# machkhoasodientu.net
KiCad netlist of a schematic drawn in Altium Designer
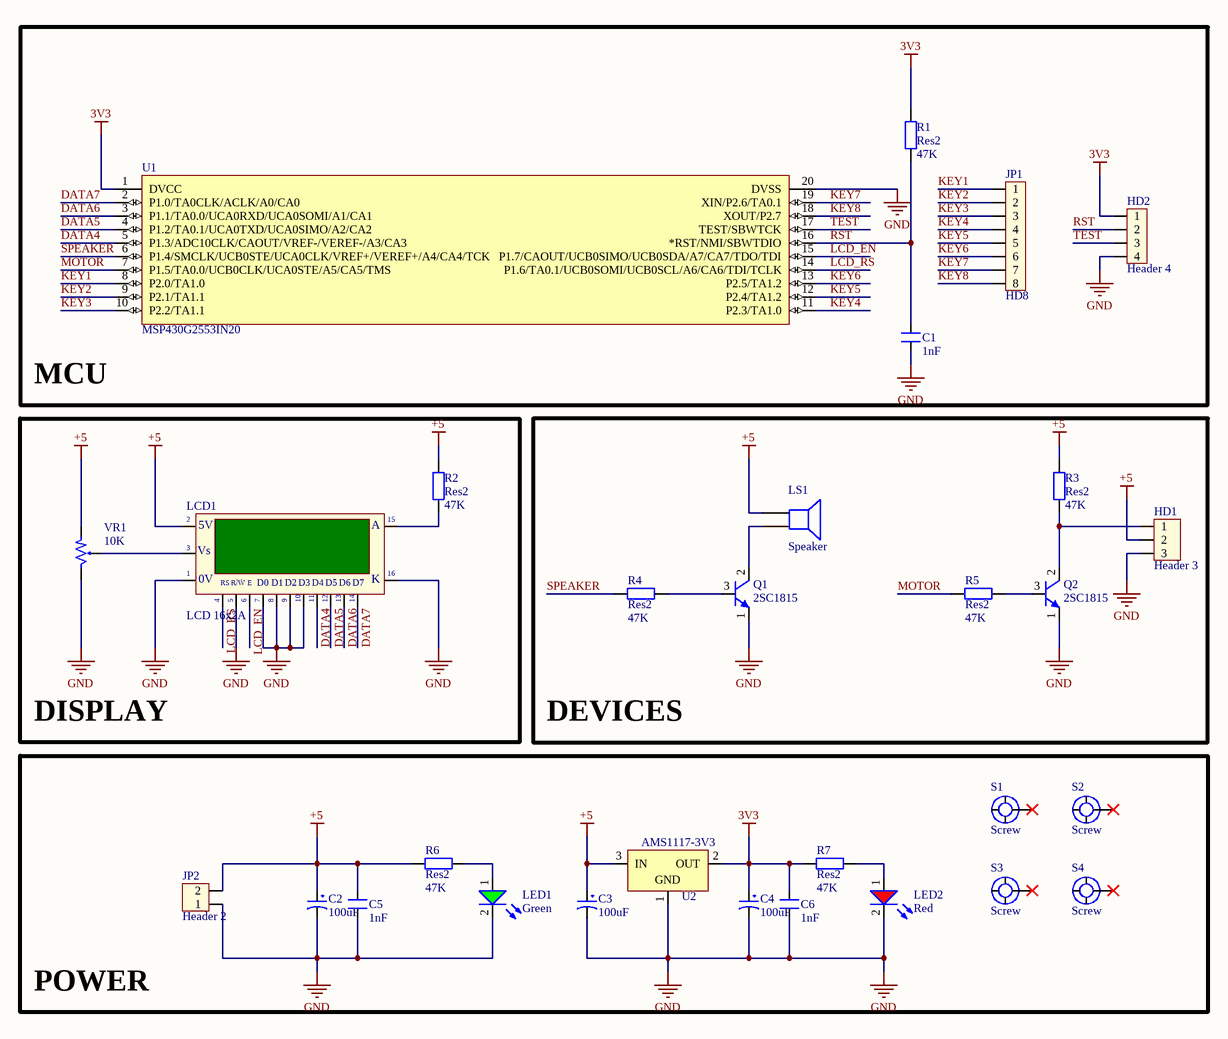
[diagram p0: machkhoasodientu.SchDoc]

(export (version "E")
  (design (tool "Eeschema 10.0.6"))
  (components
    (comp (ref "C1")
      (value "1nF")
      (footprint "CN1")
      (description "Cap np  1pF - 472pF")
      (libsource (lib "lpson") (part "CN1"))
    )
    (comp (ref "C2")
      (value "100uF")
      (footprint "CP1/2.5")
      (description "C 47uF/50V , 220uF/16V")
      (libsource (lib "lpson") (part "CP2"))
    )
    (comp (ref "C3")
      (value "100uF")
      (footprint "CP1/2.5")
      (description "C 47uF/50V , 220uF/16V")
      (libsource (lib "lpson") (part "CP2"))
    )
    (comp (ref "C4")
      (value "100uF")
      (footprint "CP1/2.5")
      (description "C 47uF/50V , 220uF/16V")
      (libsource (lib "lpson") (part "CP2"))
    )
    (comp (ref "C5")
      (value "1nF")
      (footprint "CN1")
      (description "Cap np  1pF - 472pF")
      (libsource (lib "lpson") (part "CN1"))
    )
    (comp (ref "C6")
      (value "1nF")
      (footprint "CN1")
      (description "Cap np  1pF - 472pF")
      (libsource (lib "lpson") (part "CN1"))
    )
    (comp (ref "HD1") (value "Header 3") (footprint "Header_3") (libsource (lib "lpson") (part "Header3")))
    (comp (ref "HD2") (value "Header 4") (footprint "Header_4") (libsource (lib "lpson") (part "Header4")))
    (comp (ref "JP1")
      (value "HD8")
      (footprint "Header_8")
      (description "Header 8")
      (fields (field (name "CREAT BY") "VanDungEvn@Gmail.com"))
      (libsource (lib "lpson") (part "Header8"))
    )
    (comp (ref "JP2") (value "Header 2") (footprint "Header_2") (libsource (lib "lpson") (part "Header2")))
    (comp (ref "LCD1")
      (value "LCD 16x2A")
      (footprint "LCD16x2")
      (description "LCD dipslay 16 char, 2 line")
      (libsource (lib "lpson") (part "LCD16x2A"))
    )
    (comp (ref "LED1")
      (value "Green")
      (footprint "LED3G")
      (description "LED Green 3mm")
      (fields (field (name "Comment") "LED_G_3"))
      (libsource (lib "lpson") (part "LED_GREEN_3MM"))
    )
    (comp (ref "LED2")
      (value "Red")
      (footprint "LED3R")
      (description "LED Red 3mm")
      (fields (field (name "Comment") "LED_R_3"))
      (libsource (lib "lpson") (part "LED_RED_3MM"))
    )
    (comp (ref "LS1")
      (value "Speaker")
      (footprint "SPEAKER")
      (description "Loudspeaker")
      (fields (field (name "PUBLISHER") "Altium Limited"))
      (libsource (lib "My Library") (part "Speaker"))
    )
    (comp (ref "Q1")
      (value "2SC1815")
      (footprint "2SC1815")
      (description "Trans NPN 50V 150mA TO-92")
      (libsource (lib "lpson") (part "2SC1815"))
    )
    (comp (ref "Q2")
      (value "2SC1815")
      (footprint "2SC1815")
      (description "Trans NPN 50V 150mA TO-92")
      (libsource (lib "lpson") (part "2SC1815"))
    )
    (comp (ref "R1")
      (value "Res2")
      (footprint "RES 1/4W CFR25")
      (description "Resistor")
      (fields (field (name "ALTIUM_VALUE") "47K") (field (name "PUBLISHER") "Altium Limited"))
      (libsource (lib "lpson") (part "Res2"))
    )
    (comp (ref "R2")
      (value "Res2")
      (footprint "RES 1/4W CFR25")
      (description "Resistor")
      (fields (field (name "ALTIUM_VALUE") "47K") (field (name "PUBLISHER") "Altium Limited"))
      (libsource (lib "lpson") (part "Res2"))
    )
    (comp (ref "R3")
      (value "Res2")
      (footprint "RES 1/4W CFR25")
      (description "Resistor")
      (fields (field (name "ALTIUM_VALUE") "47K") (field (name "PUBLISHER") "Altium Limited"))
      (libsource (lib "lpson") (part "Res2"))
    )
    (comp (ref "R4")
      (value "Res2")
      (footprint "RES 1/4W CFR25")
      (description "Resistor")
      (fields (field (name "ALTIUM_VALUE") "47K") (field (name "PUBLISHER") "Altium Limited"))
      (libsource (lib "") (part "Res2_1"))
    )
    (comp (ref "R5")
      (value "Res2")
      (footprint "RES 1/4W CFR25")
      (description "Resistor")
      (fields (field (name "ALTIUM_VALUE") "47K") (field (name "PUBLISHER") "Altium Limited"))
      (libsource (lib "") (part "Res2_1"))
    )
    (comp (ref "R6")
      (value "Res2")
      (footprint "RES 1/4W CFR25")
      (description "Resistor")
      (fields (field (name "ALTIUM_VALUE") "47K") (field (name "PUBLISHER") "Altium Limited"))
      (libsource (lib "") (part "Res2_1"))
    )
    (comp (ref "R7")
      (value "Res2")
      (footprint "RES 1/4W CFR25")
      (description "Resistor")
      (fields (field (name "ALTIUM_VALUE") "47K") (field (name "PUBLISHER") "Altium Limited"))
      (libsource (lib "") (part "Res2_1"))
    )
    (comp (ref "S1") (value "Screw") (footprint "Screw 3 small") (libsource (lib "lpson") (part "Screw")))
    (comp (ref "S2") (value "Screw") (footprint "Screw 3 small") (libsource (lib "lpson") (part "Screw")))
    (comp (ref "S3") (value "Screw") (footprint "Screw 3 small") (libsource (lib "lpson") (part "Screw")))
    (comp (ref "S4") (value "Screw") (footprint "Screw 3 small") (libsource (lib "lpson") (part "Screw")))
    (comp (ref "U1")
      (value "MSP430G2553IN20")
      (footprint "MSP430G2553")
      (description "MCU 16bit 16KB 1.8-3.6V 16MHz DIP20")
      (libsource (lib "lpson") (part "MSP430G2553IN20"))
    )
    (comp (ref "U2")
      (value "AMS1117-3V3")
      (footprint "AMS1117-3.3V")
      (description "Linear Voltage Regulator 3.3V 1A 15V Max SOT-223")
      (libsource (lib "lpson") (part "AMS1117-3V3"))
    )
    (comp (ref "VR1")
      (value "10K")
      (footprint "VR1")
      (description "Var Resistor")
      (libsource (lib "lpson") (part "VR2"))
    )
  )
  (nets
    (net (code "1") (name "+5") (class "Default")
      (node (ref "C2") (pin "1") (pinfunction "1_1") (pintype "passive"))
      (node (ref "C3") (pin "1") (pinfunction "1_1") (pintype "passive"))
      (node (ref "C5") (pin "2") (pinfunction "2_2") (pintype "passive"))
      (node (ref "HD1") (pin "2") (pinfunction "2_2") (pintype "passive"))
      (node (ref "JP2") (pin "2") (pinfunction "2_2") (pintype "passive"))
      (node (ref "LCD1") (pin "2") (pinfunction "VDD_2") (pintype "passive"))
      (node (ref "LS1") (pin "1") (pinfunction "1_1") (pintype "passive"))
      (node (ref "R2") (pin "2") (pinfunction "2_2") (pintype "passive"))
      (node (ref "R3") (pin "2") (pinfunction "2_2") (pintype "passive"))
      (node (ref "R6") (pin "2") (pinfunction "2_2") (pintype "passive"))
      (node (ref "U2") (pin "3") (pinfunction "IN_3") (pintype "power_in"))
      (node (ref "VR1") (pin "1") (pinfunction "1_1") (pintype "passive"))
    )
    (net (code "2") (name "/DATA4") (class "Default")
      (node (ref "LCD1") (pin "11") (pinfunction "D4_11") (pintype "passive"))
      (node (ref "U1") (pin "5") (pinfunction "P1.3/ADC10CLK/CAOUT/VREF-/VEREF-/A3/CA3_5") (pintype "bidirectional"))
    )
    (net (code "3") (name "/DATA5") (class "Default")
      (node (ref "LCD1") (pin "12") (pinfunction "D5_12") (pintype "passive"))
      (node (ref "U1") (pin "4") (pinfunction "P1.2/TA0.1/UCA0TXD/UCA0SIMO/A2/CA2_4") (pintype "bidirectional"))
    )
    (net (code "4") (name "/DATA6") (class "Default")
      (node (ref "LCD1") (pin "13") (pinfunction "D6_13") (pintype "passive"))
      (node (ref "U1") (pin "3") (pinfunction "P1.1/TA0.0/UCA0RXD/UCA0SOMI/A1/CA1_3") (pintype "bidirectional"))
    )
    (net (code "5") (name "/DATA7") (class "Default")
      (node (ref "LCD1") (pin "14") (pinfunction "D7_14") (pintype "passive"))
      (node (ref "U1") (pin "2") (pinfunction "P1.0/TA0CLK/ACLK/A0/CA0_2") (pintype "bidirectional"))
    )
    (net (code "6") (name "/KEY1") (class "Default")
      (node (ref "JP1") (pin "1") (pinfunction "1_1") (pintype "passive"))
      (node (ref "U1") (pin "8") (pinfunction "P2.0/TA1.0_8") (pintype "bidirectional"))
    )
    (net (code "7") (name "/KEY2") (class "Default")
      (node (ref "JP1") (pin "2") (pinfunction "2_2") (pintype "passive"))
      (node (ref "U1") (pin "9") (pinfunction "P2.1/TA1.1_9") (pintype "bidirectional"))
    )
    (net (code "8") (name "/KEY3") (class "Default")
      (node (ref "JP1") (pin "3") (pinfunction "3_3") (pintype "passive"))
      (node (ref "U1") (pin "10") (pinfunction "P2.2/TA1.1_10") (pintype "bidirectional"))
    )
    (net (code "9") (name "/KEY4") (class "Default")
      (node (ref "JP1") (pin "4") (pinfunction "4_4") (pintype "passive"))
      (node (ref "U1") (pin "11") (pinfunction "P2.3/TA1.0_11") (pintype "bidirectional"))
    )
    (net (code "10") (name "/KEY5") (class "Default")
      (node (ref "JP1") (pin "5") (pinfunction "5_5") (pintype "passive"))
      (node (ref "U1") (pin "12") (pinfunction "P2.4/TA1.2_12") (pintype "bidirectional"))
    )
    (net (code "11") (name "/KEY6") (class "Default")
      (node (ref "JP1") (pin "6") (pinfunction "6_6") (pintype "passive"))
      (node (ref "U1") (pin "13") (pinfunction "P2.5/TA1.2_13") (pintype "bidirectional"))
    )
    (net (code "12") (name "/KEY7") (class "Default")
      (node (ref "JP1") (pin "7") (pinfunction "7_7") (pintype "passive"))
      (node (ref "U1") (pin "19") (pinfunction "XIN/P2.6/TA0.1_19") (pintype "bidirectional"))
    )
    (net (code "13") (name "/KEY8") (class "Default")
      (node (ref "JP1") (pin "8") (pinfunction "8_8") (pintype "passive"))
      (node (ref "U1") (pin "18") (pinfunction "XOUT/P2.7_18") (pintype "bidirectional"))
    )
    (net (code "14") (name "/LCD_EN") (class "Default")
      (node (ref "LCD1") (pin "6") (pinfunction "~{EN}_6") (pintype "passive"))
      (node (ref "U1") (pin "15") (pinfunction "P1.7/CAOUT/UCB0SIMO/UCB0SDA/A7/CA7/TDO/TDI_15") (pintype "bidirectional"))
    )
    (net (code "15") (name "/LCD_RS") (class "Default")
      (node (ref "LCD1") (pin "4") (pinfunction "RS_4") (pintype "passive"))
      (node (ref "U1") (pin "14") (pinfunction "P1.6/TA0.1/UCB0SOMI/UCB0SCL/A6/CA6/TDI/TCLK_14") (pintype "bidirectional"))
    )
    (net (code "16") (name "/MOTOR") (class "Default")
      (node (ref "R5") (pin "2") (pinfunction "2_2") (pintype "passive"))
      (node (ref "U1") (pin "7") (pinfunction "P1.5/TA0.0/UCB0CLK/UCA0STE/A5/CA5/TMS_7") (pintype "bidirectional"))
    )
    (net (code "17") (name "/RST") (class "Default")
      (node (ref "C1") (pin "2") (pinfunction "2_2") (pintype "passive"))
      (node (ref "HD2") (pin "2") (pinfunction "2_2") (pintype "passive"))
      (node (ref "R1") (pin "1") (pinfunction "1_1") (pintype "passive"))
      (node (ref "U1") (pin "16") (pinfunction "*RST/NMI/SBWTDIO_16") (pintype "bidirectional"))
    )
    (net (code "18") (name "/SPEAKER") (class "Default")
      (node (ref "R4") (pin "2") (pinfunction "2_2") (pintype "passive"))
      (node (ref "U1") (pin "6") (pinfunction "P1.4/SMCLK/UCB0STE/UCA0CLK/VREF+/VEREF+/A4/CA4/TCK_6") (pintype "bidirectional"))
    )
    (net (code "19") (name "/TEST") (class "Default")
      (node (ref "HD2") (pin "3") (pinfunction "3_3") (pintype "passive"))
      (node (ref "U1") (pin "17") (pinfunction "TEST/SBWTCK_17") (pintype "bidirectional"))
    )
    (net (code "20") (name "3V3") (class "Default")
      (node (ref "C4") (pin "1") (pinfunction "1_1") (pintype "passive"))
      (node (ref "C6") (pin "2") (pinfunction "2_2") (pintype "passive"))
      (node (ref "HD2") (pin "1") (pinfunction "1_1") (pintype "passive"))
      (node (ref "R1") (pin "2") (pinfunction "2_2") (pintype "passive"))
      (node (ref "R7") (pin "2") (pinfunction "2_2") (pintype "passive"))
      (node (ref "U1") (pin "1") (pinfunction "DVCC_1") (pintype "power_in"))
      (node (ref "U2") (pin "2") (pinfunction "OUT_2") (pintype "power_in"))
    )
    (net (code "21") (name "GND") (class "Default")
      (node (ref "C1") (pin "1") (pinfunction "1_1") (pintype "passive"))
      (node (ref "C2") (pin "2") (pinfunction "2_2") (pintype "passive"))
      (node (ref "C3") (pin "2") (pinfunction "2_2") (pintype "passive"))
      (node (ref "C4") (pin "2") (pinfunction "2_2") (pintype "passive"))
      (node (ref "C5") (pin "1") (pinfunction "1_1") (pintype "passive"))
      (node (ref "C6") (pin "1") (pinfunction "1_1") (pintype "passive"))
      (node (ref "HD1") (pin "3") (pinfunction "3_3") (pintype "passive"))
      (node (ref "HD2") (pin "4") (pinfunction "4_4") (pintype "passive"))
      (node (ref "JP2") (pin "1") (pinfunction "1_1") (pintype "passive"))
      (node (ref "LCD1") (pin "1") (pinfunction "GND_1") (pintype "passive"))
      (node (ref "LCD1") (pin "10") (pinfunction "D3_10") (pintype "passive"))
      (node (ref "LCD1") (pin "16") (pinfunction "K_16") (pintype "passive"))
      (node (ref "LCD1") (pin "5") (pinfunction "R/~{W}_5") (pintype "passive"))
      (node (ref "LCD1") (pin "7") (pinfunction "D0_7") (pintype "passive"))
      (node (ref "LCD1") (pin "8") (pinfunction "D1_8") (pintype "passive"))
      (node (ref "LCD1") (pin "9") (pinfunction "D2_9") (pintype "passive"))
      (node (ref "LED1") (pin "2") (pinfunction "K_2") (pintype "passive"))
      (node (ref "LED2") (pin "2") (pinfunction "K_2") (pintype "passive"))
      (node (ref "Q1") (pin "1") (pinfunction "E_1") (pintype "passive"))
      (node (ref "Q2") (pin "1") (pinfunction "E_1") (pintype "passive"))
      (node (ref "U1") (pin "20") (pinfunction "DVSS_20") (pintype "power_in"))
      (node (ref "U2") (pin "1") (pinfunction "GND_1") (pintype "power_in"))
      (node (ref "VR1") (pin "3") (pinfunction "3_3") (pintype "passive"))
    )
    (net (code "22") (name "Net-(LCD1-A)") (class "Default")
      (node (ref "LCD1") (pin "15") (pinfunction "A_15") (pintype "passive"))
      (node (ref "R2") (pin "1") (pinfunction "1_1") (pintype "passive"))
    )
    (net (code "23") (name "Net-(LCD1-VEE)") (class "Default")
      (node (ref "LCD1") (pin "3") (pinfunction "VEE_3") (pintype "passive"))
      (node (ref "VR1") (pin "2") (pinfunction "2_2") (pintype "passive"))
    )
    (net (code "24") (name "Net-(LED1-A)") (class "Default")
      (node (ref "LED1") (pin "1") (pinfunction "A_1") (pintype "passive"))
      (node (ref "R6") (pin "1") (pinfunction "1_1") (pintype "passive"))
    )
    (net (code "25") (name "Net-(LED2-A)") (class "Default")
      (node (ref "LED2") (pin "1") (pinfunction "A_1") (pintype "passive"))
      (node (ref "R7") (pin "1") (pinfunction "1_1") (pintype "passive"))
    )
    (net (code "26") (name "Net-(Q1-B)") (class "Default")
      (node (ref "Q1") (pin "3") (pinfunction "B_3") (pintype "passive"))
      (node (ref "R4") (pin "1") (pinfunction "1_1") (pintype "passive"))
    )
    (net (code "27") (name "Net-(Q1-C)") (class "Default")
      (node (ref "LS1") (pin "2") (pinfunction "2_2") (pintype "passive"))
      (node (ref "Q1") (pin "2") (pinfunction "C_2") (pintype "passive"))
    )
    (net (code "28") (name "Net-(Q2-B)") (class "Default")
      (node (ref "Q2") (pin "3") (pinfunction "B_3") (pintype "passive"))
      (node (ref "R5") (pin "1") (pinfunction "1_1") (pintype "passive"))
    )
    (net (code "29") (name "Net-(Q2-C)") (class "Default")
      (node (ref "HD1") (pin "1") (pinfunction "1_1") (pintype "passive"))
      (node (ref "Q2") (pin "2") (pinfunction "C_2") (pintype "passive"))
      (node (ref "R3") (pin "1") (pinfunction "1_1") (pintype "passive"))
    )
    (net (code "30") (name "unconnected-(S1-Pad1)") (class "Default")
      (node (ref "S1") (pin "1") (pinfunction "1_1") (pintype "passive+no_connect"))
    )
    (net (code "31") (name "unconnected-(S2-Pad1)") (class "Default")
      (node (ref "S2") (pin "1") (pinfunction "1_1") (pintype "passive+no_connect"))
    )
    (net (code "32") (name "unconnected-(S3-Pad1)") (class "Default")
      (node (ref "S3") (pin "1") (pinfunction "1_1") (pintype "passive+no_connect"))
    )
    (net (code "33") (name "unconnected-(S4-Pad1)") (class "Default")
      (node (ref "S4") (pin "1") (pinfunction "1_1") (pintype "passive+no_connect"))
    )
    (net (code "34") (name "unconnected-(U2-OUT-Pad4)") (class "Default")
      (node (ref "U2") (pin "4") (pinfunction "OUT_4") (pintype "power_in"))
    )
  )
)
